# FYDP-Schematic.net
KiCad netlist of a schematic drawn in EAGLE
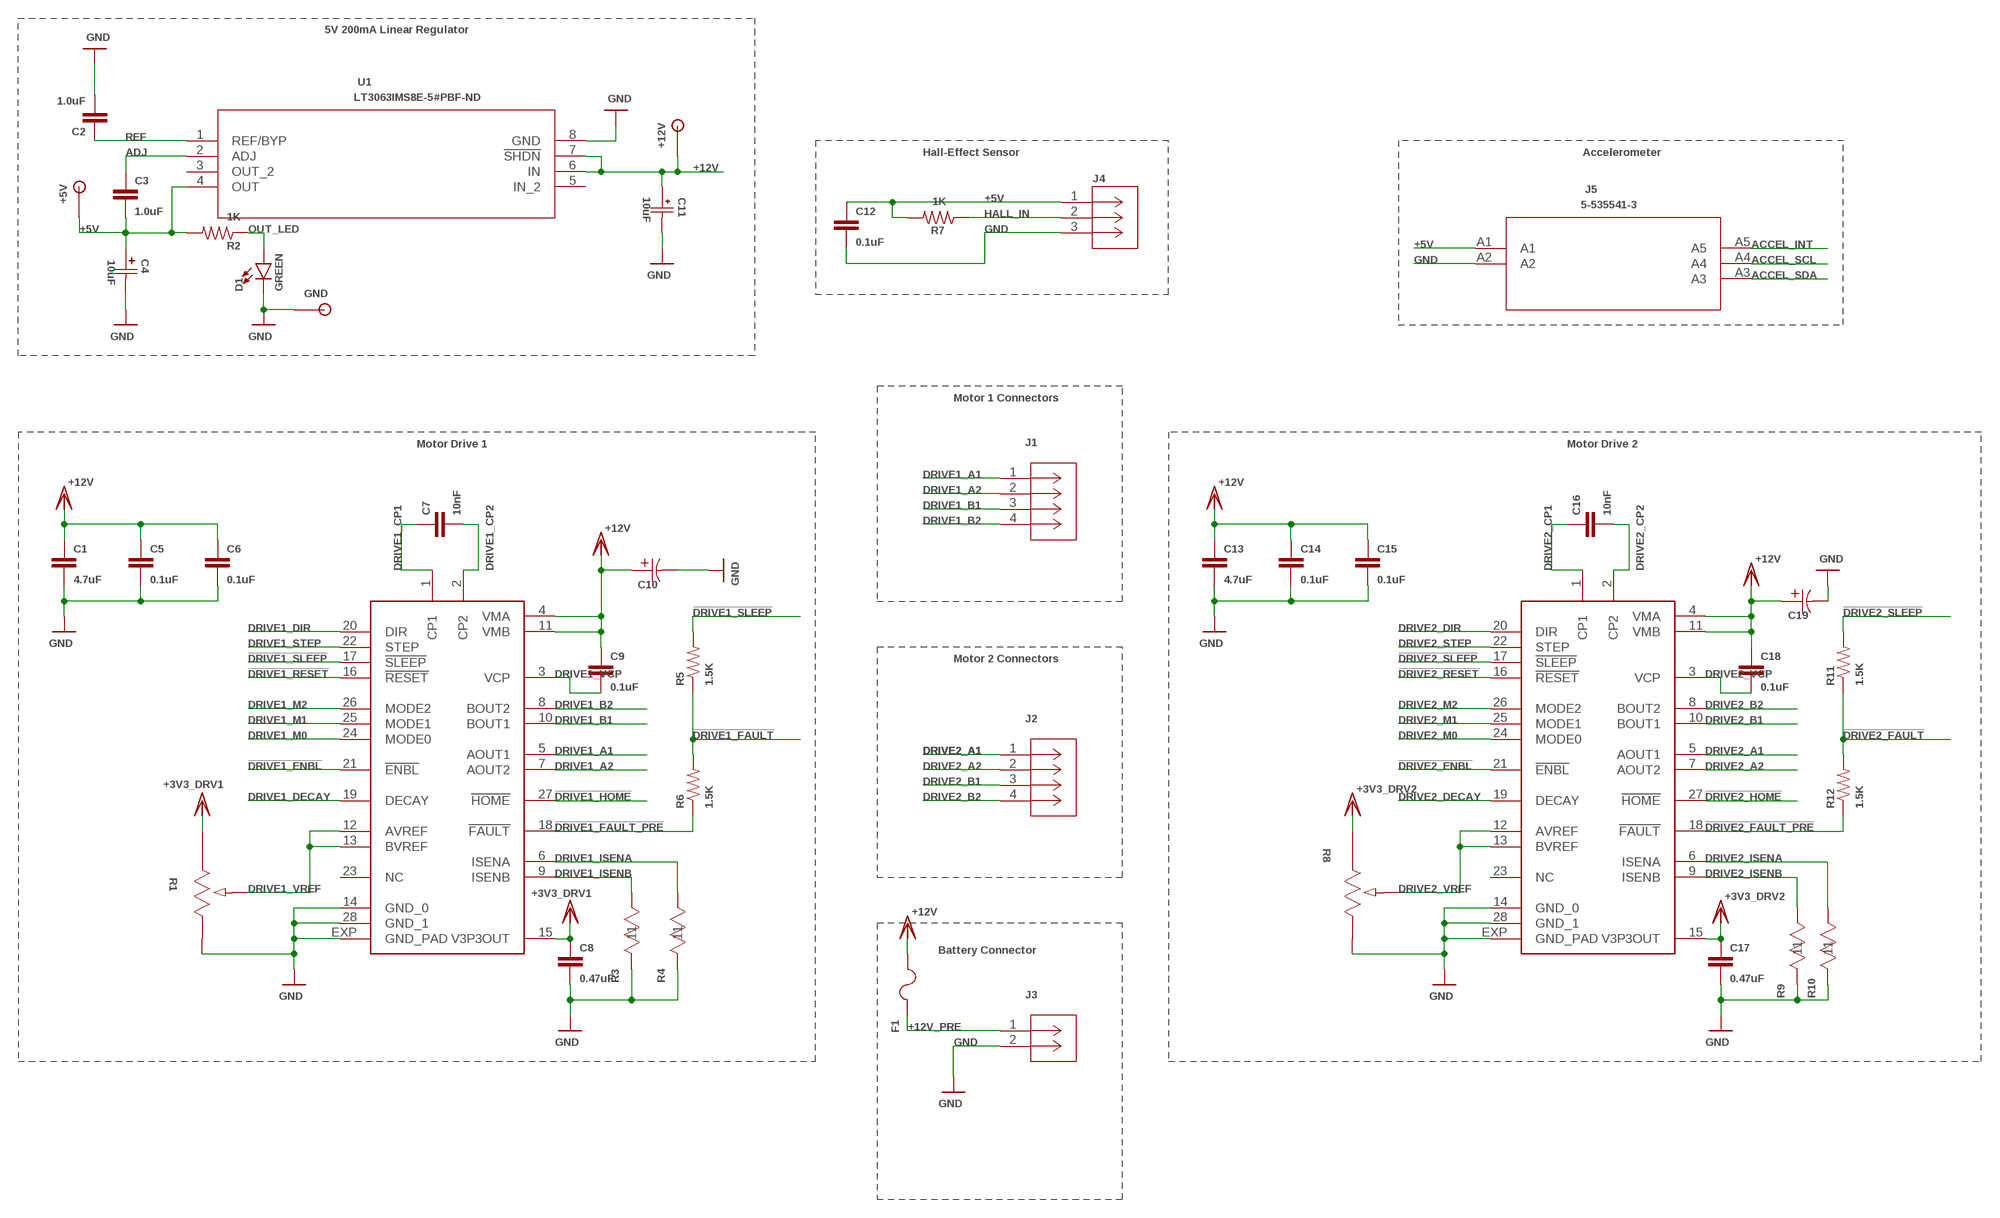
[diagram p0: schematic, sheet 1]
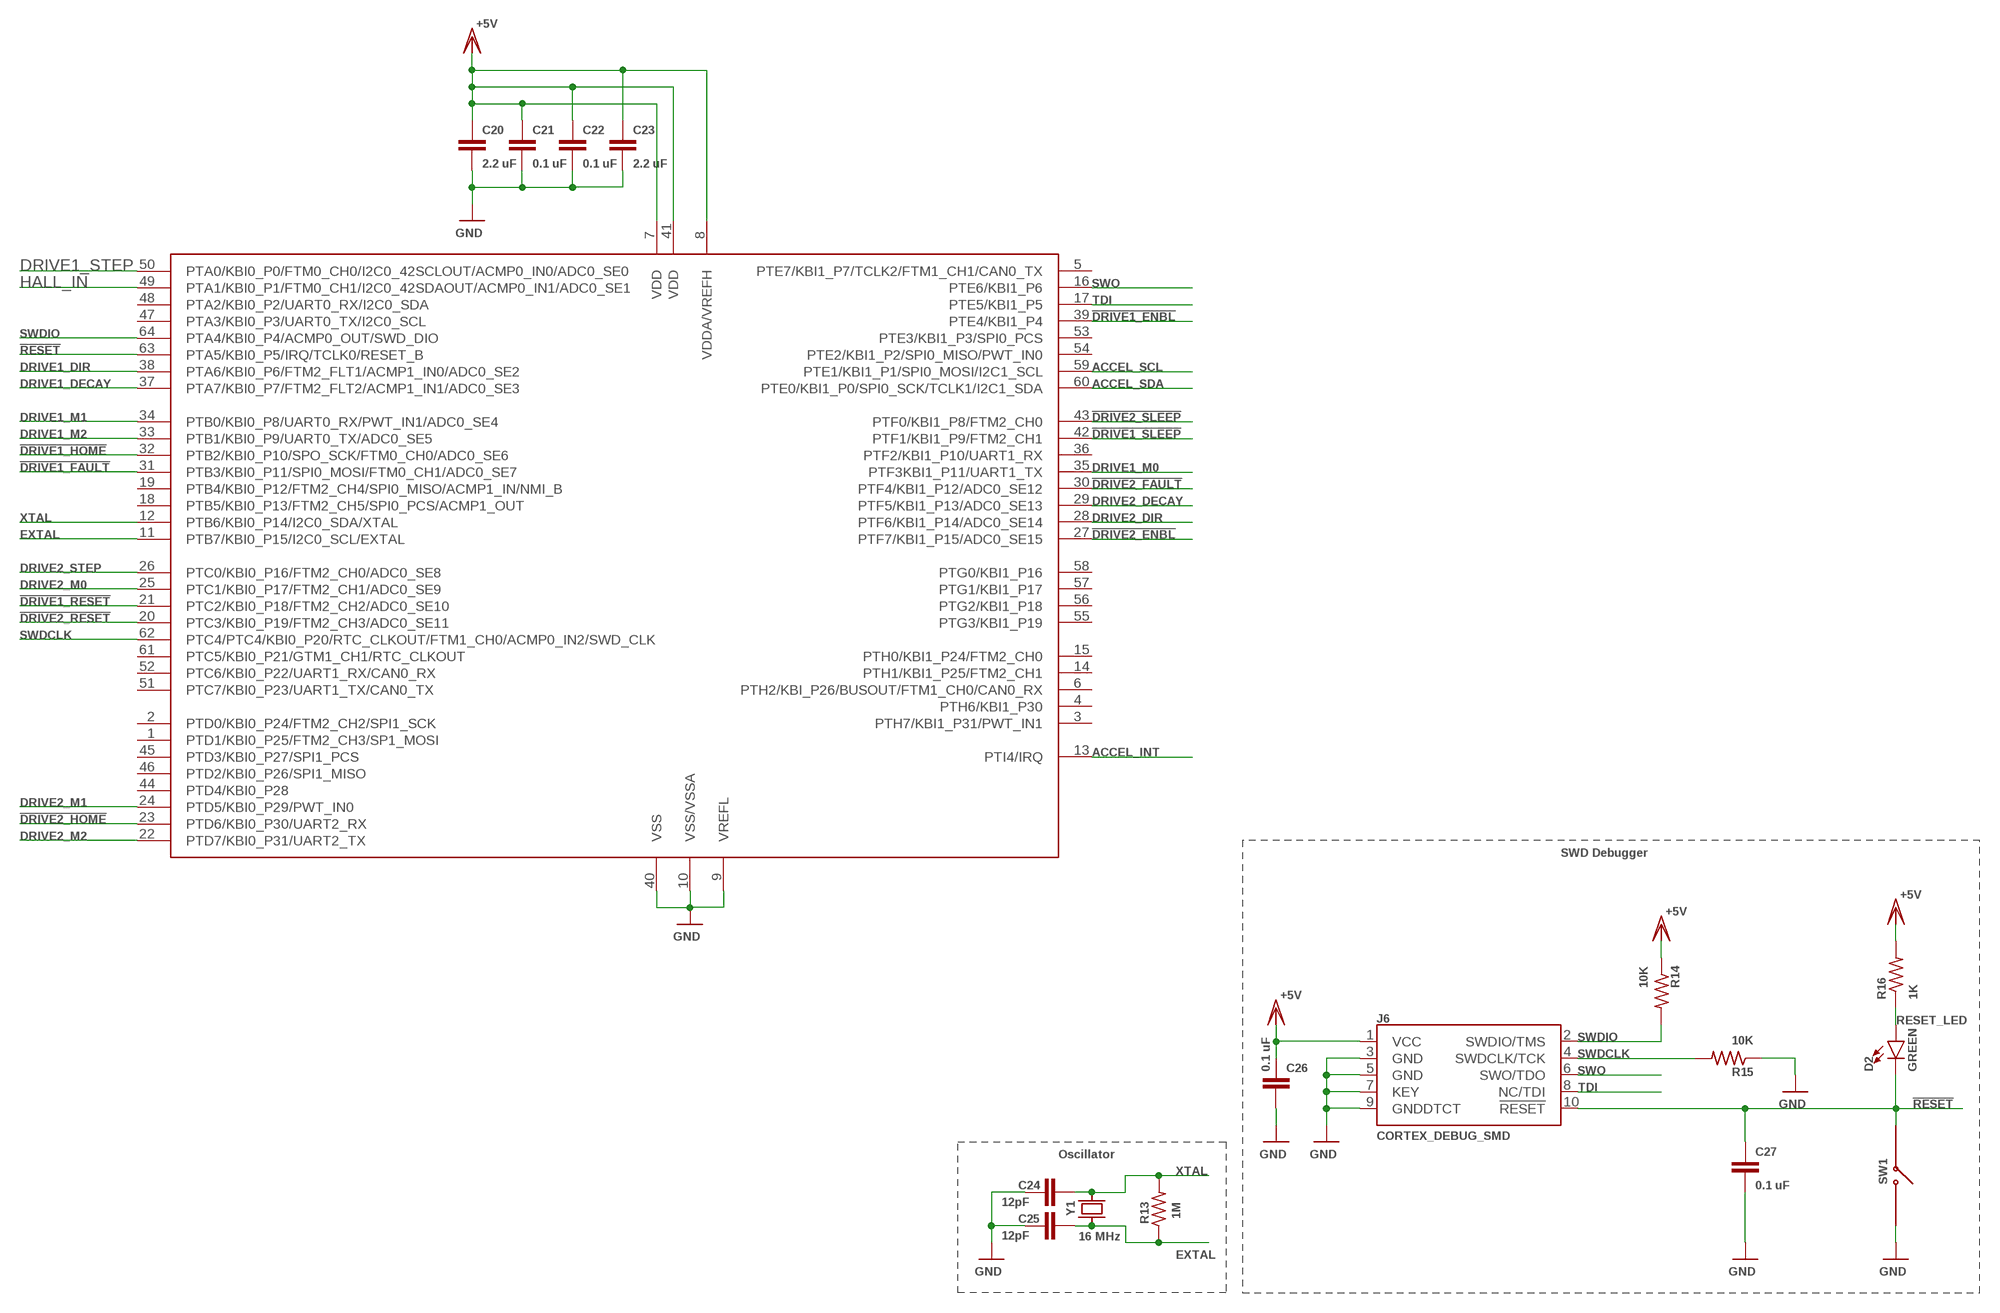
[diagram p1: schematic, sheet 2]

(export (version "E")
  (design (tool "Eeschema 10.0.6"))
  (components
    (comp (ref "C20")
      (value "2.2 uF")
      (footprint "eagle-import:0603")
      (libsource (lib "eagle-import") (part "C_0603"))
    )
    (comp (ref "C21")
      (value "0.1 uF")
      (footprint "eagle-import:0603")
      (libsource (lib "eagle-import") (part "C_0603"))
    )
    (comp (ref "C22")
      (value "0.1 uF")
      (footprint "eagle-import:0603")
      (libsource (lib "eagle-import") (part "C_0603"))
    )
    (comp (ref "C23")
      (value "2.2 uF")
      (footprint "eagle-import:0603")
      (libsource (lib "eagle-import") (part "C_0603"))
    )
    (comp (ref "C24")
      (value "12pF")
      (footprint "eagle-import:0603")
      (libsource (lib "eagle-import") (part "C_0603"))
    )
    (comp (ref "C25")
      (value "12pF")
      (footprint "eagle-import:0603")
      (libsource (lib "eagle-import") (part "C_0603"))
    )
    (comp (ref "C26")
      (value "0.1 uF")
      (footprint "eagle-import:0603")
      (libsource (lib "eagle-import") (part "C_0603"))
    )
    (comp (ref "C27")
      (value "0.1 uF")
      (footprint "eagle-import:0603")
      (libsource (lib "eagle-import") (part "C_0603"))
    )
    (comp (ref "D2")
      (value "GREEN")
      (footprint "eagle-import:LED-0603")
      (libsource (lib "eagle-import") (part "LED-GREEN0603"))
    )
    (comp (ref "J6")
      (value "CORTEX_DEBUG_SMD")
      (footprint "eagle-import:SAMTECH_FTSH-105-01")
      (libsource (lib "eagle-import") (part "CORTEX_DEBUG_SMD"))
    )
    (comp (ref "R13")
      (value "1M")
      (footprint "eagle-import:0603")
      (libsource (lib "eagle-import") (part "R_0603"))
    )
    (comp (ref "R14")
      (value "10K")
      (footprint "eagle-import:0603")
      (libsource (lib "eagle-import") (part "R_0603"))
    )
    (comp (ref "R15")
      (value "10K")
      (footprint "eagle-import:0603")
      (libsource (lib "eagle-import") (part "R_0603"))
    )
    (comp (ref "R16")
      (value "1K")
      (footprint "eagle-import:0603")
      (libsource (lib "eagle-import") (part "R_0603"))
    )
    (comp (ref "SW1")
      (value "KSR223GNCLFG")
      (footprint "eagle-import:KSR223GNCLFG")
      (libsource (lib "eagle-import") (part "KSR223GNCLFG"))
    )
    (comp (ref "U4")
      (value "S9KEA128")
      (footprint "eagle-import:S9KEA128")
      (libsource (lib "eagle-import") (part "S9KEA128"))
    )
    (comp (ref "Y1")
      (value "16 MHz")
      (footprint "eagle-import:AT-16.000MAGE-T")
      (libsource (lib "eagle-import") (part "AT-16.000MAGE-T"))
    )
    (comp (ref "+5V")
      (value "TESTPOINT")
      (footprint "eagle-import:TESTPOINT")
      (libsource (lib "eagle-import") (part "TESTPOINT"))
    )
    (comp (ref "+12V")
      (value "TESTPOINT")
      (footprint "eagle-import:TESTPOINT")
      (libsource (lib "eagle-import") (part "TESTPOINT"))
    )
    (comp (ref "C1")
      (value "4.7uF")
      (footprint "eagle-import:0603")
      (libsource (lib "eagle-import") (part "C_0603"))
    )
    (comp (ref "C2")
      (value "1.0uF")
      (footprint "eagle-import:0603")
      (libsource (lib "eagle-import") (part "1.0UF-0603-16V-10%"))
    )
    (comp (ref "C3")
      (value "1.0uF")
      (footprint "eagle-import:0603")
      (libsource (lib "eagle-import") (part "1.0UF-0603-16V-10%"))
    )
    (comp (ref "C4")
      (value "10uF")
      (footprint "eagle-import:F93-C")
      (fields (field (name "MANUFACTURER_PART_NUMBER") "F931C106MBA"))
      (libsource (lib "eagle-import") (part "F931C106MBA"))
    )
    (comp (ref "C5")
      (value "0.1uF")
      (footprint "eagle-import:0603")
      (libsource (lib "eagle-import") (part "C_0603"))
    )
    (comp (ref "C6")
      (value "0.1uF")
      (footprint "eagle-import:0603")
      (libsource (lib "eagle-import") (part "C_0603"))
    )
    (comp (ref "C7")
      (value "10nF")
      (footprint "eagle-import:0603")
      (libsource (lib "eagle-import") (part "C_0603"))
    )
    (comp (ref "C8")
      (value "0.47uF")
      (footprint "eagle-import:0603")
      (libsource (lib "eagle-import") (part "C_0603"))
    )
    (comp (ref "C9")
      (value "0.1uF")
      (footprint "eagle-import:0603")
      (libsource (lib "eagle-import") (part "C_0603"))
    )
    (comp (ref "C10")
      (value "UWX1C101MCL1GB")
      (footprint "eagle-import:PCAP_6.3X5.4-ELECT")
      (libsource (lib "eagle-import") (part "UWX1C101MCL1GB"))
    )
    (comp (ref "C11")
      (value "10uF")
      (footprint "eagle-import:G-188")
      (fields (field (name "MANUFACTURER_PART_NUMBER") "GRM188C81C106MA73D"))
      (libsource (lib "eagle-import") (part "GRM188C81C106MA73D"))
    )
    (comp (ref "C12")
      (value "0.1uF")
      (footprint "eagle-import:0603")
      (libsource (lib "eagle-import") (part "C_0603"))
    )
    (comp (ref "C13")
      (value "4.7uF")
      (footprint "eagle-import:0603")
      (libsource (lib "eagle-import") (part "C_0603"))
    )
    (comp (ref "C14")
      (value "0.1uF")
      (footprint "eagle-import:0603")
      (libsource (lib "eagle-import") (part "C_0603"))
    )
    (comp (ref "C15")
      (value "0.1uF")
      (footprint "eagle-import:0603")
      (libsource (lib "eagle-import") (part "C_0603"))
    )
    (comp (ref "C16")
      (value "10nF")
      (footprint "eagle-import:0603")
      (libsource (lib "eagle-import") (part "C_0603"))
    )
    (comp (ref "C17")
      (value "0.47uF")
      (footprint "eagle-import:0603")
      (libsource (lib "eagle-import") (part "C_0603"))
    )
    (comp (ref "C18")
      (value "0.1uF")
      (footprint "eagle-import:0603")
      (libsource (lib "eagle-import") (part "C_0603"))
    )
    (comp (ref "C19")
      (value "UWX1C101MCL1GB")
      (footprint "eagle-import:PCAP_6.3X5.4-ELECT")
      (libsource (lib "eagle-import") (part "UWX1C101MCL1GB"))
    )
    (comp (ref "D1")
      (value "GREEN")
      (footprint "eagle-import:LED-0603")
      (libsource (lib "eagle-import") (part "LED-GREEN0603"))
    )
    (comp (ref "F1")
      (value "1210L110/12WR")
      (footprint "eagle-import:1210LSERIES")
      (fields (field (name "MANUFACTURER_PART_NUMBER") "1210L11012WR"))
      (libsource (lib "eagle-import") (part "1210L110/12WR"))
    )
    (comp (ref "GND")
      (value "TESTPOINT")
      (footprint "eagle-import:TESTPOINT")
      (libsource (lib "eagle-import") (part "TESTPOINT"))
    )
    (comp (ref "J1")
      (value "2029030-4")
      (footprint "eagle-import:CONN_2029030-4")
      (fields (field (name "MANUFACTURER_PART_NUMBER") "20290304"))
      (libsource (lib "eagle-import") (part "2029030-4"))
    )
    (comp (ref "J2")
      (value "2029030-4")
      (footprint "eagle-import:CONN_2029030-4")
      (fields (field (name "MANUFACTURER_PART_NUMBER") "20290304"))
      (libsource (lib "eagle-import") (part "2029030-4"))
    )
    (comp (ref "J3")
      (value "2029030-2")
      (footprint "eagle-import:CONN_2029030-2")
      (fields (field (name "MANUFACTURER_PART_NUMBER") "20290302"))
      (libsource (lib "eagle-import") (part "2029030-2"))
    )
    (comp (ref "J4")
      (value "2029030-3")
      (footprint "eagle-import:CONN_2029030-3")
      (fields (field (name "MANUFACTURER_PART_NUMBER") "20290303"))
      (libsource (lib "eagle-import") (part "2029030-3"))
    )
    (comp (ref "J5")
      (value "5-535541-3")
      (footprint "eagle-import:5-535541-3")
      (fields (field (name "MANUFACTURER_PART_NUMBER") "55355413"))
      (libsource (lib "eagle-import") (part "5-535541-3"))
    )
    (comp (ref "R1")
      (value "3314G-1-103E")
      (footprint "eagle-import:POT_3314G")
      (fields (field (name "MANUFACTURER_PART_NUMBER") "3314G1103E"))
      (libsource (lib "eagle-import") (part "3314G-1-103E"))
    )
    (comp (ref "R2")
      (value "1K")
      (footprint "eagle-import:0603")
      (libsource (lib "eagle-import") (part "R_0603"))
    )
    (comp (ref "R3")
      (value "CSR1206FKR200")
      (footprint "eagle-import:STA_CSR1206")
      (libsource (lib "eagle-import") (part "CSR1206FKR200"))
    )
    (comp (ref "R4")
      (value "CSR1206FKR200")
      (footprint "eagle-import:STA_CSR1206")
      (libsource (lib "eagle-import") (part "CSR1206FKR200"))
    )
    (comp (ref "R5")
      (value "1.5K")
      (footprint "eagle-import:0603")
      (libsource (lib "eagle-import") (part "R_0603"))
    )
    (comp (ref "R6")
      (value "1.5K")
      (footprint "eagle-import:0603")
      (libsource (lib "eagle-import") (part "R_0603"))
    )
    (comp (ref "R7")
      (value "1K")
      (footprint "eagle-import:0603")
      (libsource (lib "eagle-import") (part "R_0603"))
    )
    (comp (ref "R8")
      (value "3314G-1-103E")
      (footprint "eagle-import:POT_3314G")
      (fields (field (name "MANUFACTURER_PART_NUMBER") "3314G1103E"))
      (libsource (lib "eagle-import") (part "3314G-1-103E"))
    )
    (comp (ref "R9")
      (value "CSR1206FKR200")
      (footprint "eagle-import:STA_CSR1206")
      (libsource (lib "eagle-import") (part "CSR1206FKR200"))
    )
    (comp (ref "R10")
      (value "CSR1206FKR200")
      (footprint "eagle-import:STA_CSR1206")
      (libsource (lib "eagle-import") (part "CSR1206FKR200"))
    )
    (comp (ref "R11")
      (value "1.5K")
      (footprint "eagle-import:0603")
      (libsource (lib "eagle-import") (part "R_0603"))
    )
    (comp (ref "R12")
      (value "1.5K")
      (footprint "eagle-import:0603")
      (libsource (lib "eagle-import") (part "R_0603"))
    )
    (comp (ref "U1")
      (value "LT3063IMS8E-5#PBF-ND")
      (footprint "eagle-import:MSOP-8_MS")
      (fields (field (name "MANUFACTURER_PART_NUMBER") "lt3063ims8e#pbf"))
      (libsource (lib "eagle-import") (part "LT3063IMS8EPBF"))
    )
    (comp (ref "U2")
      (value "DRV8825PWP")
      (footprint "eagle-import:TSSOP-28")
      (libsource (lib "eagle-import") (part "DRV8825PWP"))
    )
    (comp (ref "U3")
      (value "DRV8825PWP")
      (footprint "eagle-import:TSSOP-28")
      (libsource (lib "eagle-import") (part "DRV8825PWP"))
    )
  )
  (nets
    (net (code "1") (name "+3V3_DRV1") (class "Default")
      (node (ref "C8") (pin "1") (pinfunction "1_1") (pintype "passive"))
      (node (ref "R1") (pin "1") (pinfunction "1_1") (pintype "passive"))
      (node (ref "U3") (pin "15") (pinfunction "V3P3OUT_15") (pintype "output"))
    )
    (net (code "2") (name "+3V3_DRV2") (class "Default")
      (node (ref "C17") (pin "1") (pinfunction "1_1") (pintype "passive"))
      (node (ref "R8") (pin "1") (pinfunction "1_1") (pintype "passive"))
      (node (ref "U2") (pin "15") (pinfunction "V3P3OUT_15") (pintype "output"))
    )
    (net (code "3") (name "+5V") (class "Default")
      (node (ref "+5V") (pin "TP") (pinfunction "1_TP") (pintype "bidirectional"))
      (node (ref "C12") (pin "1") (pinfunction "1_1") (pintype "passive"))
      (node (ref "C20") (pin "1") (pinfunction "1_1") (pintype "passive"))
      (node (ref "C21") (pin "1") (pinfunction "1_1") (pintype "passive"))
      (node (ref "C22") (pin "1") (pinfunction "1_1") (pintype "passive"))
      (node (ref "C23") (pin "1") (pinfunction "1_1") (pintype "passive"))
      (node (ref "C26") (pin "1") (pinfunction "1_1") (pintype "passive"))
      (node (ref "C3") (pin "2") (pinfunction "2_2") (pintype "passive"))
      (node (ref "C4") (pin "POS") (pinfunction "1_POS") (pintype "passive"))
      (node (ref "J4") (pin "1") (pinfunction "1_1") (pintype "passive"))
      (node (ref "J5") (pin "A1") (pinfunction "A1_A1") (pintype "passive"))
      (node (ref "J6") (pin "1") (pinfunction "VCC_1") (pintype "bidirectional"))
      (node (ref "R14") (pin "1") (pinfunction "1_1") (pintype "passive"))
      (node (ref "R16") (pin "2") (pinfunction "2_2") (pintype "passive"))
      (node (ref "R2") (pin "2") (pinfunction "2_2") (pintype "passive"))
      (node (ref "R7") (pin "2") (pinfunction "2_2") (pintype "passive"))
      (node (ref "U1") (pin "4") (pinfunction "OUT_4") (pintype "output"))
      (node (ref "U4") (pin "41") (pinfunction "VDD_41") (pintype "bidirectional"))
      (node (ref "U4") (pin "7") (pinfunction "VDD_7") (pintype "bidirectional"))
      (node (ref "U4") (pin "8") (pinfunction "VDDA/VREFH_8") (pintype "bidirectional"))
    )
    (net (code "4") (name "+12V") (class "Default")
      (node (ref "+12V") (pin "TP") (pinfunction "1_TP") (pintype "bidirectional"))
      (node (ref "C1") (pin "1") (pinfunction "1_1") (pintype "passive"))
      (node (ref "C10") (pin "1") (pinfunction "11_1") (pintype "passive"))
      (node (ref "C11") (pin "PWR") (pinfunction "PWR_PWR") (pintype "passive"))
      (node (ref "C13") (pin "1") (pinfunction "1_1") (pintype "passive"))
      (node (ref "C14") (pin "1") (pinfunction "1_1") (pintype "passive"))
      (node (ref "C15") (pin "1") (pinfunction "1_1") (pintype "passive"))
      (node (ref "C18") (pin "1") (pinfunction "1_1") (pintype "passive"))
      (node (ref "C19") (pin "1") (pinfunction "11_1") (pintype "passive"))
      (node (ref "C5") (pin "1") (pinfunction "1_1") (pintype "passive"))
      (node (ref "C6") (pin "1") (pinfunction "1_1") (pintype "passive"))
      (node (ref "C9") (pin "1") (pinfunction "1_1") (pintype "passive"))
      (node (ref "F1") (pin "2") (pinfunction "2_2") (pintype "passive"))
      (node (ref "U1") (pin "6") (pinfunction "IN_6") (pintype "input"))
      (node (ref "U1") (pin "7") (pinfunction "~{SHDN}_7") (pintype "output"))
      (node (ref "U2") (pin "11") (pinfunction "VMB_11") (pintype "bidirectional"))
      (node (ref "U2") (pin "4") (pinfunction "VMA_4") (pintype "bidirectional"))
      (node (ref "U3") (pin "11") (pinfunction "VMB_11") (pintype "bidirectional"))
      (node (ref "U3") (pin "4") (pinfunction "VMA_4") (pintype "bidirectional"))
    )
    (net (code "5") (name "+12V_PRE") (class "Default")
      (node (ref "F1") (pin "1") (pinfunction "1_1") (pintype "passive"))
      (node (ref "J3") (pin "1") (pinfunction "1_1") (pintype "bidirectional"))
    )
    (net (code "6") (name "ACCEL_INT") (class "Default")
      (node (ref "J5") (pin "A5") (pinfunction "A5_A5") (pintype "passive"))
      (node (ref "U4") (pin "13") (pinfunction "PTI4/IRQ_13") (pintype "bidirectional"))
    )
    (net (code "7") (name "ACCEL_SCL") (class "Default")
      (node (ref "J5") (pin "A4") (pinfunction "A4_A4") (pintype "passive"))
      (node (ref "U4") (pin "59") (pinfunction "PTE1/KBI1_P1/SPI0_MOSI/I2C1_SCL_59") (pintype "bidirectional"))
    )
    (net (code "8") (name "ACCEL_SDA") (class "Default")
      (node (ref "J5") (pin "A3") (pinfunction "A3_A3") (pintype "passive"))
      (node (ref "U4") (pin "60") (pinfunction "PTE0/KBI1_P0/SPI0_SCK/TCLK1/I2C1_SDA_60") (pintype "bidirectional"))
    )
    (net (code "9") (name "ADJ") (class "Default")
      (node (ref "C3") (pin "1") (pinfunction "1_1") (pintype "passive"))
      (node (ref "U1") (pin "2") (pinfunction "ADJ_2") (pintype "passive"))
    )
    (net (code "10") (name "DRIVE1_A1") (class "Default")
      (node (ref "J1") (pin "1") (pinfunction "1_1") (pintype "passive"))
      (node (ref "U3") (pin "5") (pinfunction "AOUT1_5") (pintype "output"))
    )
    (net (code "11") (name "DRIVE1_A2") (class "Default")
      (node (ref "J1") (pin "2") (pinfunction "2_2") (pintype "passive"))
      (node (ref "U3") (pin "7") (pinfunction "AOUT2_7") (pintype "output"))
    )
    (net (code "12") (name "DRIVE1_B1") (class "Default")
      (node (ref "J1") (pin "3") (pinfunction "3_3") (pintype "passive"))
      (node (ref "U3") (pin "10") (pinfunction "BOUT1_10") (pintype "output"))
    )
    (net (code "13") (name "DRIVE1_B2") (class "Default")
      (node (ref "J1") (pin "4") (pinfunction "4_4") (pintype "passive"))
      (node (ref "U3") (pin "8") (pinfunction "BOUT2_8") (pintype "output"))
    )
    (net (code "14") (name "DRIVE1_CP1") (class "Default")
      (node (ref "C7") (pin "1") (pinfunction "1_1") (pintype "passive"))
      (node (ref "U3") (pin "1") (pinfunction "CP1_1") (pintype "bidirectional"))
    )
    (net (code "15") (name "DRIVE1_CP2") (class "Default")
      (node (ref "C7") (pin "2") (pinfunction "2_2") (pintype "passive"))
      (node (ref "U3") (pin "2") (pinfunction "CP2_2") (pintype "bidirectional"))
    )
    (net (code "16") (name "DRIVE1_DECAY") (class "Default")
      (node (ref "U3") (pin "19") (pinfunction "DECAY_19") (pintype "input"))
      (node (ref "U4") (pin "37") (pinfunction "PTA7/KBI0_P7/FTM2_FLT2/ACMP1_IN1/ADC0_SE3_37") (pintype "bidirectional"))
    )
    (net (code "17") (name "DRIVE1_DIR") (class "Default")
      (node (ref "U3") (pin "20") (pinfunction "DIR_20") (pintype "input"))
      (node (ref "U4") (pin "38") (pinfunction "PTA6/KBI0_P6/FTM2_FLT1/ACMP1_IN0/ADC0_SE2_38") (pintype "bidirectional"))
    )
    (net (code "18") (name "DRIVE1_ISENA") (class "Default")
      (node (ref "R4") (pin "2") (pinfunction "22_2") (pintype "passive"))
      (node (ref "U3") (pin "6") (pinfunction "ISENA_6") (pintype "output"))
    )
    (net (code "19") (name "DRIVE1_ISENB") (class "Default")
      (node (ref "R3") (pin "2") (pinfunction "22_2") (pintype "passive"))
      (node (ref "U3") (pin "9") (pinfunction "ISENB_9") (pintype "output"))
    )
    (net (code "20") (name "DRIVE1_M0") (class "Default")
      (node (ref "U3") (pin "24") (pinfunction "MODE0_24") (pintype "input"))
      (node (ref "U4") (pin "35") (pinfunction "PTF3KBI1_P11/UART1_TX_35") (pintype "bidirectional"))
    )
    (net (code "21") (name "DRIVE1_M1") (class "Default")
      (node (ref "U3") (pin "25") (pinfunction "MODE1_25") (pintype "input"))
      (node (ref "U4") (pin "34") (pinfunction "PTB0/KBI0_P8/UART0_RX/PWT_IN1/ADC0_SE4_34") (pintype "bidirectional"))
    )
    (net (code "22") (name "DRIVE1_M2") (class "Default")
      (node (ref "U3") (pin "26") (pinfunction "MODE2_26") (pintype "input"))
      (node (ref "U4") (pin "33") (pinfunction "PTB1/KBI0_P9/UART0_TX/ADC0_SE5_33") (pintype "bidirectional"))
    )
    (net (code "23") (name "DRIVE1_STEP") (class "Default")
      (node (ref "U3") (pin "22") (pinfunction "STEP_22") (pintype "input"))
      (node (ref "U4") (pin "50") (pinfunction "PTA0/KBI0_P0/FTM0_CH0/I2C0_42SCLOUT/ACMP0_IN0/ADC0_SE0_50") (pintype "bidirectional"))
    )
    (net (code "24") (name "DRIVE1_VCP") (class "Default")
      (node (ref "C9") (pin "2") (pinfunction "2_2") (pintype "passive"))
      (node (ref "U3") (pin "3") (pinfunction "VCP_3") (pintype "bidirectional"))
    )
    (net (code "25") (name "DRIVE1_VREF") (class "Default")
      (node (ref "R1") (pin "2") (pinfunction "2_2") (pintype "passive"))
      (node (ref "U3") (pin "12") (pinfunction "AVREF_12") (pintype "input"))
      (node (ref "U3") (pin "13") (pinfunction "BVREF_13") (pintype "input"))
    )
    (net (code "26") (name "DRIVE2_A1") (class "Default")
      (node (ref "J2") (pin "1") (pinfunction "1_1") (pintype "passive"))
      (node (ref "U2") (pin "5") (pinfunction "AOUT1_5") (pintype "output"))
    )
    (net (code "27") (name "DRIVE2_A2") (class "Default")
      (node (ref "J2") (pin "2") (pinfunction "2_2") (pintype "passive"))
      (node (ref "U2") (pin "7") (pinfunction "AOUT2_7") (pintype "output"))
    )
    (net (code "28") (name "DRIVE2_B1") (class "Default")
      (node (ref "J2") (pin "3") (pinfunction "3_3") (pintype "passive"))
      (node (ref "U2") (pin "10") (pinfunction "BOUT1_10") (pintype "output"))
    )
    (net (code "29") (name "DRIVE2_B2") (class "Default")
      (node (ref "J2") (pin "4") (pinfunction "4_4") (pintype "passive"))
      (node (ref "U2") (pin "8") (pinfunction "BOUT2_8") (pintype "output"))
    )
    (net (code "30") (name "DRIVE2_CP1") (class "Default")
      (node (ref "C16") (pin "1") (pinfunction "1_1") (pintype "passive"))
      (node (ref "U2") (pin "1") (pinfunction "CP1_1") (pintype "bidirectional"))
    )
    (net (code "31") (name "DRIVE2_CP2") (class "Default")
      (node (ref "C16") (pin "2") (pinfunction "2_2") (pintype "passive"))
      (node (ref "U2") (pin "2") (pinfunction "CP2_2") (pintype "bidirectional"))
    )
    (net (code "32") (name "DRIVE2_DECAY") (class "Default")
      (node (ref "U2") (pin "19") (pinfunction "DECAY_19") (pintype "input"))
      (node (ref "U4") (pin "29") (pinfunction "PTF5/KBI1_P13/ADC0_SE13_29") (pintype "bidirectional"))
    )
    (net (code "33") (name "DRIVE2_DIR") (class "Default")
      (node (ref "U2") (pin "20") (pinfunction "DIR_20") (pintype "input"))
      (node (ref "U4") (pin "28") (pinfunction "PTF6/KBI1_P14/ADC0_SE14_28") (pintype "bidirectional"))
    )
    (net (code "34") (name "DRIVE2_ISENA") (class "Default")
      (node (ref "R10") (pin "2") (pinfunction "22_2") (pintype "passive"))
      (node (ref "U2") (pin "6") (pinfunction "ISENA_6") (pintype "output"))
    )
    (net (code "35") (name "DRIVE2_ISENB") (class "Default")
      (node (ref "R9") (pin "2") (pinfunction "22_2") (pintype "passive"))
      (node (ref "U2") (pin "9") (pinfunction "ISENB_9") (pintype "output"))
    )
    (net (code "36") (name "DRIVE2_M0") (class "Default")
      (node (ref "U2") (pin "24") (pinfunction "MODE0_24") (pintype "input"))
      (node (ref "U4") (pin "25") (pinfunction "PTC1/KBI0_P17/FTM2_CH1/ADC0_SE9_25") (pintype "bidirectional"))
    )
    (net (code "37") (name "DRIVE2_M1") (class "Default")
      (node (ref "U2") (pin "25") (pinfunction "MODE1_25") (pintype "input"))
      (node (ref "U4") (pin "24") (pinfunction "PTD5/KBI0_P29/PWT_IN0_24") (pintype "bidirectional"))
    )
    (net (code "38") (name "DRIVE2_M2") (class "Default")
      (node (ref "U2") (pin "26") (pinfunction "MODE2_26") (pintype "input"))
      (node (ref "U4") (pin "22") (pinfunction "PTD7/KBI0_P31/UART2_TX_22") (pintype "bidirectional"))
    )
    (net (code "39") (name "DRIVE2_STEP") (class "Default")
      (node (ref "U2") (pin "22") (pinfunction "STEP_22") (pintype "input"))
      (node (ref "U4") (pin "26") (pinfunction "PTC0/KBI0_P16/FTM2_CH0/ADC0_SE8_26") (pintype "bidirectional"))
    )
    (net (code "40") (name "DRIVE2_VCP") (class "Default")
      (node (ref "C18") (pin "2") (pinfunction "2_2") (pintype "passive"))
      (node (ref "U2") (pin "3") (pinfunction "VCP_3") (pintype "bidirectional"))
    )
    (net (code "41") (name "DRIVE2_VREF") (class "Default")
      (node (ref "R8") (pin "2") (pinfunction "2_2") (pintype "passive"))
      (node (ref "U2") (pin "12") (pinfunction "AVREF_12") (pintype "input"))
      (node (ref "U2") (pin "13") (pinfunction "BVREF_13") (pintype "input"))
    )
    (net (code "42") (name "EXTAL") (class "Default")
      (node (ref "C25") (pin "1") (pinfunction "1_1") (pintype "passive"))
      (node (ref "R13") (pin "1") (pinfunction "1_1") (pintype "passive"))
      (node (ref "U4") (pin "11") (pinfunction "PTB7/KBI0_P15/I2C0_SCL/EXTAL_11") (pintype "bidirectional"))
      (node (ref "Y1") (pin "1") (pinfunction "1_1") (pintype "passive"))
    )
    (net (code "43") (name "GND") (class "Default")
      (node (ref "C1") (pin "2") (pinfunction "2_2") (pintype "passive"))
      (node (ref "C10") (pin "2") (pinfunction "22_2") (pintype "passive"))
      (node (ref "C11") (pin "GND") (pinfunction "GND_GND") (pintype "passive"))
      (node (ref "C12") (pin "2") (pinfunction "2_2") (pintype "passive"))
      (node (ref "C13") (pin "2") (pinfunction "2_2") (pintype "passive"))
      (node (ref "C14") (pin "2") (pinfunction "2_2") (pintype "passive"))
      (node (ref "C15") (pin "2") (pinfunction "2_2") (pintype "passive"))
      (node (ref "C17") (pin "2") (pinfunction "2_2") (pintype "passive"))
      (node (ref "C19") (pin "2") (pinfunction "22_2") (pintype "passive"))
      (node (ref "C2") (pin "2") (pinfunction "2_2") (pintype "passive"))
      (node (ref "C20") (pin "2") (pinfunction "2_2") (pintype "passive"))
      (node (ref "C21") (pin "2") (pinfunction "2_2") (pintype "passive"))
      (node (ref "C22") (pin "2") (pinfunction "2_2") (pintype "passive"))
      (node (ref "C23") (pin "2") (pinfunction "2_2") (pintype "passive"))
      (node (ref "C24") (pin "2") (pinfunction "2_2") (pintype "passive"))
      (node (ref "C25") (pin "2") (pinfunction "2_2") (pintype "passive"))
      (node (ref "C26") (pin "2") (pinfunction "2_2") (pintype "passive"))
      (node (ref "C27") (pin "2") (pinfunction "2_2") (pintype "passive"))
      (node (ref "C4") (pin "GND") (pinfunction "2_GND") (pintype "passive"))
      (node (ref "C5") (pin "2") (pinfunction "2_2") (pintype "passive"))
      (node (ref "C6") (pin "2") (pinfunction "2_2") (pintype "passive"))
      (node (ref "C8") (pin "2") (pinfunction "2_2") (pintype "passive"))
      (node (ref "D1") (pin "C") (pinfunction "C_C") (pintype "passive"))
      (node (ref "GND") (pin "TP") (pinfunction "1_TP") (pintype "bidirectional"))
      (node (ref "J3") (pin "2") (pinfunction "2_2") (pintype "bidirectional"))
      (node (ref "J4") (pin "3") (pinfunction "3_3") (pintype "passive"))
      (node (ref "J5") (pin "A2") (pinfunction "A2_A2") (pintype "passive"))
      (node (ref "J6") (pin "3") (pinfunction "GND_3") (pintype "bidirectional"))
      (node (ref "J6") (pin "5") (pinfunction "GND_5") (pintype "bidirectional"))
      (node (ref "J6") (pin "7") (pinfunction "KEY_7") (pintype "bidirectional"))
      (node (ref "J6") (pin "9") (pinfunction "GNDDTCT_9") (pintype "bidirectional"))
      (node (ref "R1") (pin "3") (pinfunction "3_3") (pintype "passive"))
      (node (ref "R10") (pin "1") (pinfunction "11_1") (pintype "passive"))
      (node (ref "R15") (pin "1") (pinfunction "1_1") (pintype "passive"))
      (node (ref "R3") (pin "1") (pinfunction "11_1") (pintype "passive"))
      (node (ref "R4") (pin "1") (pinfunction "11_1") (pintype "passive"))
      (node (ref "R8") (pin "3") (pinfunction "3_3") (pintype "passive"))
      (node (ref "R9") (pin "1") (pinfunction "11_1") (pintype "passive"))
      (node (ref "SW1") (pin "2") (pinfunction "2_2") (pintype "bidirectional"))
      (node (ref "U1") (pin "8") (pinfunction "GND_8") (pintype "power_in"))
      (node (ref "U2") (pin "14") (pinfunction "GND_0_14") (pintype "bidirectional"))
      (node (ref "U2") (pin "28") (pinfunction "GND_1_28") (pintype "bidirectional"))
      (node (ref "U2") (pin "EXP") (pinfunction "GND_PAD_EXP") (pintype "bidirectional"))
      (node (ref "U3") (pin "14") (pinfunction "GND_0_14") (pintype "bidirectional"))
      (node (ref "U3") (pin "28") (pinfunction "GND_1_28") (pintype "bidirectional"))
      (node (ref "U3") (pin "EXP") (pinfunction "GND_PAD_EXP") (pintype "bidirectional"))
      (node (ref "U4") (pin "10") (pinfunction "VSS/VSSA_10") (pintype "bidirectional"))
      (node (ref "U4") (pin "40") (pinfunction "VSS_40") (pintype "bidirectional"))
      (node (ref "U4") (pin "9") (pinfunction "VREFL_9") (pintype "bidirectional"))
    )
    (net (code "44") (name "HALL_IN") (class "Default")
      (node (ref "J4") (pin "2") (pinfunction "2_2") (pintype "passive"))
      (node (ref "R7") (pin "1") (pinfunction "1_1") (pintype "passive"))
      (node (ref "U4") (pin "49") (pinfunction "PTA1/KBI0_P1/FTM0_CH1/I2C0_42SDAOUT/ACMP0_IN1/ADC0_SE1_49") (pintype "bidirectional"))
    )
    (net (code "45") (name "OUT_LED") (class "Default")
      (node (ref "D1") (pin "A") (pinfunction "A_A") (pintype "passive"))
      (node (ref "R2") (pin "1") (pinfunction "1_1") (pintype "passive"))
    )
    (net (code "46") (name "REF") (class "Default")
      (node (ref "C2") (pin "1") (pinfunction "1_1") (pintype "passive"))
      (node (ref "U1") (pin "1") (pinfunction "REF/BYP_1") (pintype "passive"))
    )
    (net (code "47") (name "RESET_LED") (class "Default")
      (node (ref "D2") (pin "A") (pinfunction "A_A") (pintype "passive"))
      (node (ref "R16") (pin "1") (pinfunction "1_1") (pintype "passive"))
    )
    (net (code "48") (name "SWDCLK") (class "Default")
      (node (ref "J6") (pin "4") (pinfunction "SWDCLK/TCK_4") (pintype "bidirectional"))
      (node (ref "R15") (pin "2") (pinfunction "2_2") (pintype "passive"))
      (node (ref "U4") (pin "62") (pinfunction "PTC4/PTC4/KBI0_P20/RTC_CLKOUT/FTM1_CH0/ACMP0_IN2/SWD_CLK_62") (pintype "bidirectional"))
    )
    (net (code "49") (name "SWDIO") (class "Default")
      (node (ref "J6") (pin "2") (pinfunction "SWDIO/TMS_2") (pintype "bidirectional"))
      (node (ref "R14") (pin "2") (pinfunction "2_2") (pintype "passive"))
      (node (ref "U4") (pin "64") (pinfunction "PTA4/KBI0_P4/ACMP0_OUT/SWD_DIO_64") (pintype "bidirectional"))
    )
    (net (code "50") (name "SWO") (class "Default")
      (node (ref "J6") (pin "6") (pinfunction "SWO/TDO_6") (pintype "bidirectional"))
      (node (ref "U4") (pin "16") (pinfunction "PTE6/KBI1_P6_16") (pintype "bidirectional"))
    )
    (net (code "51") (name "TDI") (class "Default")
      (node (ref "J6") (pin "8") (pinfunction "NC/TDI_8") (pintype "bidirectional"))
      (node (ref "U4") (pin "17") (pinfunction "PTE5/KBI1_P5_17") (pintype "bidirectional"))
    )
    (net (code "52") (name "XTAL") (class "Default")
      (node (ref "C24") (pin "1") (pinfunction "1_1") (pintype "passive"))
      (node (ref "R13") (pin "2") (pinfunction "2_2") (pintype "passive"))
      (node (ref "U4") (pin "12") (pinfunction "PTB6/KBI0_P14/I2C0_SDA/XTAL_12") (pintype "bidirectional"))
      (node (ref "Y1") (pin "2") (pinfunction "2_2") (pintype "passive"))
    )
    (net (code "53") (name "unconnected-(U1-IN_2-Pad5)") (class "Default")
      (node (ref "U1") (pin "5") (pinfunction "IN_2_5") (pintype "input"))
    )
    (net (code "54") (name "unconnected-(U1-OUT_2-Pad3)") (class "Default")
      (node (ref "U1") (pin "3") (pinfunction "OUT_2_3") (pintype "output"))
    )
    (net (code "55") (name "unconnected-(U2-NC-Pad23)") (class "Default")
      (node (ref "U2") (pin "23") (pinfunction "NC_23") (pintype "bidirectional"))
    )
    (net (code "56") (name "unconnected-(U3-NC-Pad23)") (class "Default")
      (node (ref "U3") (pin "23") (pinfunction "NC_23") (pintype "bidirectional"))
    )
    (net (code "57") (name "unconnected-(U4-PTA2{slash}KBI0_P2{slash}UART0_RX{slash}I2C0_SDA-Pad48)") (class "Default")
      (node (ref "U4") (pin "48") (pinfunction "PTA2/KBI0_P2/UART0_RX/I2C0_SDA_48") (pintype "bidirectional"))
    )
    (net (code "58") (name "unconnected-(U4-PTA3{slash}KBI0_P3{slash}UART0_TX{slash}I2C0_SCL-Pad47)") (class "Default")
      (node (ref "U4") (pin "47") (pinfunction "PTA3/KBI0_P3/UART0_TX/I2C0_SCL_47") (pintype "bidirectional"))
    )
    (net (code "59") (name "unconnected-(U4-PTB4{slash}KBI0_P12{slash}FTM2_CH4{slash}SPI0_MISO{slash}ACMP1_IN{slash}NMI_B-Pad19)") (class "Default")
      (node (ref "U4") (pin "19") (pinfunction "PTB4/KBI0_P12/FTM2_CH4/SPI0_MISO/ACMP1_IN/NMI_B_19") (pintype "bidirectional"))
    )
    (net (code "60") (name "unconnected-(U4-PTB5{slash}KBI0_P13{slash}FTM2_CH5{slash}SPI0_PCS{slash}ACMP1_OUT-Pad18)") (class "Default")
      (node (ref "U4") (pin "18") (pinfunction "PTB5/KBI0_P13/FTM2_CH5/SPI0_PCS/ACMP1_OUT_18") (pintype "bidirectional"))
    )
    (net (code "61") (name "unconnected-(U4-PTC5{slash}KBI0_P21{slash}GTM1_CH1{slash}RTC_CLKOUT-Pad61)") (class "Default")
      (node (ref "U4") (pin "61") (pinfunction "PTC5/KBI0_P21/GTM1_CH1/RTC_CLKOUT_61") (pintype "bidirectional"))
    )
    (net (code "62") (name "unconnected-(U4-PTC6{slash}KBI0_P22{slash}UART1_RX{slash}CAN0_RX-Pad52)") (class "Default")
      (node (ref "U4") (pin "52") (pinfunction "PTC6/KBI0_P22/UART1_RX/CAN0_RX_52") (pintype "bidirectional"))
    )
    (net (code "63") (name "unconnected-(U4-PTC7{slash}KBI0_P23{slash}UART1_TX{slash}CAN0_TX-Pad51)") (class "Default")
      (node (ref "U4") (pin "51") (pinfunction "PTC7/KBI0_P23/UART1_TX/CAN0_TX_51") (pintype "bidirectional"))
    )
    (net (code "64") (name "unconnected-(U4-PTD0{slash}KBI0_P24{slash}FTM2_CH2{slash}SPI1_SCK-Pad2)") (class "Default")
      (node (ref "U4") (pin "2") (pinfunction "PTD0/KBI0_P24/FTM2_CH2/SPI1_SCK_2") (pintype "bidirectional"))
    )
    (net (code "65") (name "unconnected-(U4-PTD1{slash}KBI0_P25{slash}FTM2_CH3{slash}SP1_MOSI-Pad1)") (class "Default")
      (node (ref "U4") (pin "1") (pinfunction "PTD1/KBI0_P25/FTM2_CH3/SP1_MOSI_1") (pintype "bidirectional"))
    )
    (net (code "66") (name "unconnected-(U4-PTD2{slash}KBI0_P26{slash}SPI1_MISO-Pad46)") (class "Default")
      (node (ref "U4") (pin "46") (pinfunction "PTD2/KBI0_P26/SPI1_MISO_46") (pintype "bidirectional"))
    )
    (net (code "67") (name "unconnected-(U4-PTD3{slash}KBI0_P27{slash}SPI1_PCS-Pad45)") (class "Default")
      (node (ref "U4") (pin "45") (pinfunction "PTD3/KBI0_P27/SPI1_PCS_45") (pintype "bidirectional"))
    )
    (net (code "68") (name "unconnected-(U4-PTD4{slash}KBI0_P28-Pad44)") (class "Default")
      (node (ref "U4") (pin "44") (pinfunction "PTD4/KBI0_P28_44") (pintype "bidirectional"))
    )
    (net (code "69") (name "unconnected-(U4-PTE2{slash}KBI1_P2{slash}SPI0_MISO{slash}PWT_IN0-Pad54)") (class "Default")
      (node (ref "U4") (pin "54") (pinfunction "PTE2/KBI1_P2/SPI0_MISO/PWT_IN0_54") (pintype "bidirectional"))
    )
    (net (code "70") (name "unconnected-(U4-PTE3{slash}KBI1_P3{slash}SPI0_PCS-Pad53)") (class "Default")
      (node (ref "U4") (pin "53") (pinfunction "PTE3/KBI1_P3/SPI0_PCS_53") (pintype "bidirectional"))
    )
    (net (code "71") (name "unconnected-(U4-PTE7{slash}KBI1_P7{slash}TCLK2{slash}FTM1_CH1{slash}CAN0_TX-Pad5)") (class "Default")
      (node (ref "U4") (pin "5") (pinfunction "PTE7/KBI1_P7/TCLK2/FTM1_CH1/CAN0_TX_5") (pintype "bidirectional"))
    )
    (net (code "72") (name "unconnected-(U4-PTF2{slash}KBI1_P10{slash}UART1_RX-Pad36)") (class "Default")
      (node (ref "U4") (pin "36") (pinfunction "PTF2/KBI1_P10/UART1_RX_36") (pintype "bidirectional"))
    )
    (net (code "73") (name "unconnected-(U4-PTG0{slash}KBI1_P16-Pad58)") (class "Default")
      (node (ref "U4") (pin "58") (pinfunction "PTG0/KBI1_P16_58") (pintype "bidirectional"))
    )
    (net (code "74") (name "unconnected-(U4-PTG1{slash}KBI1_P17-Pad57)") (class "Default")
      (node (ref "U4") (pin "57") (pinfunction "PTG1/KBI1_P17_57") (pintype "bidirectional"))
    )
    (net (code "75") (name "unconnected-(U4-PTG2{slash}KBI1_P18-Pad56)") (class "Default")
      (node (ref "U4") (pin "56") (pinfunction "PTG2/KBI1_P18_56") (pintype "bidirectional"))
    )
    (net (code "76") (name "unconnected-(U4-PTG3{slash}KBI1_P19-Pad55)") (class "Default")
      (node (ref "U4") (pin "55") (pinfunction "PTG3/KBI1_P19_55") (pintype "bidirectional"))
    )
    (net (code "77") (name "unconnected-(U4-PTH0{slash}KBI1_P24{slash}FTM2_CH0-Pad15)") (class "Default")
      (node (ref "U4") (pin "15") (pinfunction "PTH0/KBI1_P24/FTM2_CH0_15") (pintype "bidirectional"))
    )
    (net (code "78") (name "unconnected-(U4-PTH1{slash}KBI1_P25{slash}FTM2_CH1-Pad14)") (class "Default")
      (node (ref "U4") (pin "14") (pinfunction "PTH1/KBI1_P25/FTM2_CH1_14") (pintype "bidirectional"))
    )
    (net (code "79") (name "unconnected-(U4-PTH2{slash}KBI_P26{slash}BUSOUT{slash}FTM1_CH0{slash}CAN0_RX-Pad6)") (class "Default")
      (node (ref "U4") (pin "6") (pinfunction "PTH2/KBI_P26/BUSOUT/FTM1_CH0/CAN0_RX_6") (pintype "bidirectional"))
    )
    (net (code "80") (name "unconnected-(U4-PTH6{slash}KBI1_P30-Pad4)") (class "Default")
      (node (ref "U4") (pin "4") (pinfunction "PTH6/KBI1_P30_4") (pintype "bidirectional"))
    )
    (net (code "81") (name "unconnected-(U4-PTH7{slash}KBI1_P31{slash}PWT_IN1-Pad3)") (class "Default")
      (node (ref "U4") (pin "3") (pinfunction "PTH7/KBI1_P31/PWT_IN1_3") (pintype "bidirectional"))
    )
    (net (code "82") (name "~{DRIVE1_ENBL}") (class "Default")
      (node (ref "U3") (pin "21") (pinfunction "~{ENBL}_21") (pintype "bidirectional"))
      (node (ref "U4") (pin "39") (pinfunction "PTE4/KBI1_P4_39") (pintype "bidirectional"))
    )
    (net (code "83") (name "~{DRIVE1_FAULT_PRE}") (class "Default")
      (node (ref "R6") (pin "1") (pinfunction "1_1") (pintype "passive"))
      (node (ref "U3") (pin "18") (pinfunction "~{FAULT}_18") (pintype "bidirectional"))
    )
    (net (code "84") (name "~{DRIVE1_FAULT}") (class "Default")
      (node (ref "R5") (pin "1") (pinfunction "1_1") (pintype "passive"))
      (node (ref "R6") (pin "2") (pinfunction "2_2") (pintype "passive"))
      (node (ref "U4") (pin "31") (pinfunction "PTB3/KBI0_P11/SPI0_MOSI/FTM0_CH1/ADC0_SE7_31") (pintype "bidirectional"))
    )
    (net (code "85") (name "~{DRIVE1_HOME}") (class "Default")
      (node (ref "U3") (pin "27") (pinfunction "~{HOME}_27") (pintype "bidirectional"))
      (node (ref "U4") (pin "32") (pinfunction "PTB2/KBI0_P10/SPO_SCK/FTM0_CH0/ADC0_SE6_32") (pintype "bidirectional"))
    )
    (net (code "86") (name "~{DRIVE1_RESET}") (class "Default")
      (node (ref "U3") (pin "16") (pinfunction "~{RESET}_16") (pintype "bidirectional"))
      (node (ref "U4") (pin "21") (pinfunction "PTC2/KBI0_P18/FTM2_CH2/ADC0_SE10_21") (pintype "bidirectional"))
    )
    (net (code "87") (name "~{DRIVE1_SLEEP}") (class "Default")
      (node (ref "R5") (pin "2") (pinfunction "2_2") (pintype "passive"))
      (node (ref "U3") (pin "17") (pinfunction "~{SLEEP}_17") (pintype "bidirectional"))
      (node (ref "U4") (pin "42") (pinfunction "PTF1/KBI1_P9/FTM2_CH1_42") (pintype "bidirectional"))
    )
    (net (code "88") (name "~{DRIVE2_ENBL}") (class "Default")
      (node (ref "U2") (pin "21") (pinfunction "~{ENBL}_21") (pintype "bidirectional"))
      (node (ref "U4") (pin "27") (pinfunction "PTF7/KBI1_P15/ADC0_SE15_27") (pintype "bidirectional"))
    )
    (net (code "89") (name "~{DRIVE2_FAULT_PRE}") (class "Default")
      (node (ref "R12") (pin "1") (pinfunction "1_1") (pintype "passive"))
      (node (ref "U2") (pin "18") (pinfunction "~{FAULT}_18") (pintype "bidirectional"))
    )
    (net (code "90") (name "~{DRIVE2_FAULT}") (class "Default")
      (node (ref "R11") (pin "1") (pinfunction "1_1") (pintype "passive"))
      (node (ref "R12") (pin "2") (pinfunction "2_2") (pintype "passive"))
      (node (ref "U4") (pin "30") (pinfunction "PTF4/KBI1_P12/ADC0_SE12_30") (pintype "bidirectional"))
    )
    (net (code "91") (name "~{DRIVE2_HOME}") (class "Default")
      (node (ref "U2") (pin "27") (pinfunction "~{HOME}_27") (pintype "bidirectional"))
      (node (ref "U4") (pin "23") (pinfunction "PTD6/KBI0_P30/UART2_RX_23") (pintype "bidirectional"))
    )
    (net (code "92") (name "~{DRIVE2_RESET}") (class "Default")
      (node (ref "U2") (pin "16") (pinfunction "~{RESET}_16") (pintype "bidirectional"))
      (node (ref "U4") (pin "20") (pinfunction "PTC3/KBI0_P19/FTM2_CH3/ADC0_SE11_20") (pintype "bidirectional"))
    )
    (net (code "93") (name "~{DRIVE2_SLEEP}") (class "Default")
      (node (ref "R11") (pin "2") (pinfunction "2_2") (pintype "passive"))
      (node (ref "U2") (pin "17") (pinfunction "~{SLEEP}_17") (pintype "bidirectional"))
      (node (ref "U4") (pin "43") (pinfunction "PTF0/KBI1_P8/FTM2_CH0_43") (pintype "bidirectional"))
    )
    (net (code "94") (name "~{RESET}") (class "Default")
      (node (ref "C27") (pin "1") (pinfunction "1_1") (pintype "passive"))
      (node (ref "D2") (pin "C") (pinfunction "C_C") (pintype "passive"))
      (node (ref "J6") (pin "10") (pinfunction "~{RESET}_10") (pintype "bidirectional"))
      (node (ref "SW1") (pin "1") (pinfunction "1_1") (pintype "bidirectional"))
      (node (ref "U4") (pin "63") (pinfunction "PTA5/KBI0_P5/IRQ/TCLK0/RESET_B_63") (pintype "bidirectional"))
    )
  )
)
